# 10w_CREE_LED_driver_auto.net
KiCad netlist of a schematic drawn in EAGLE
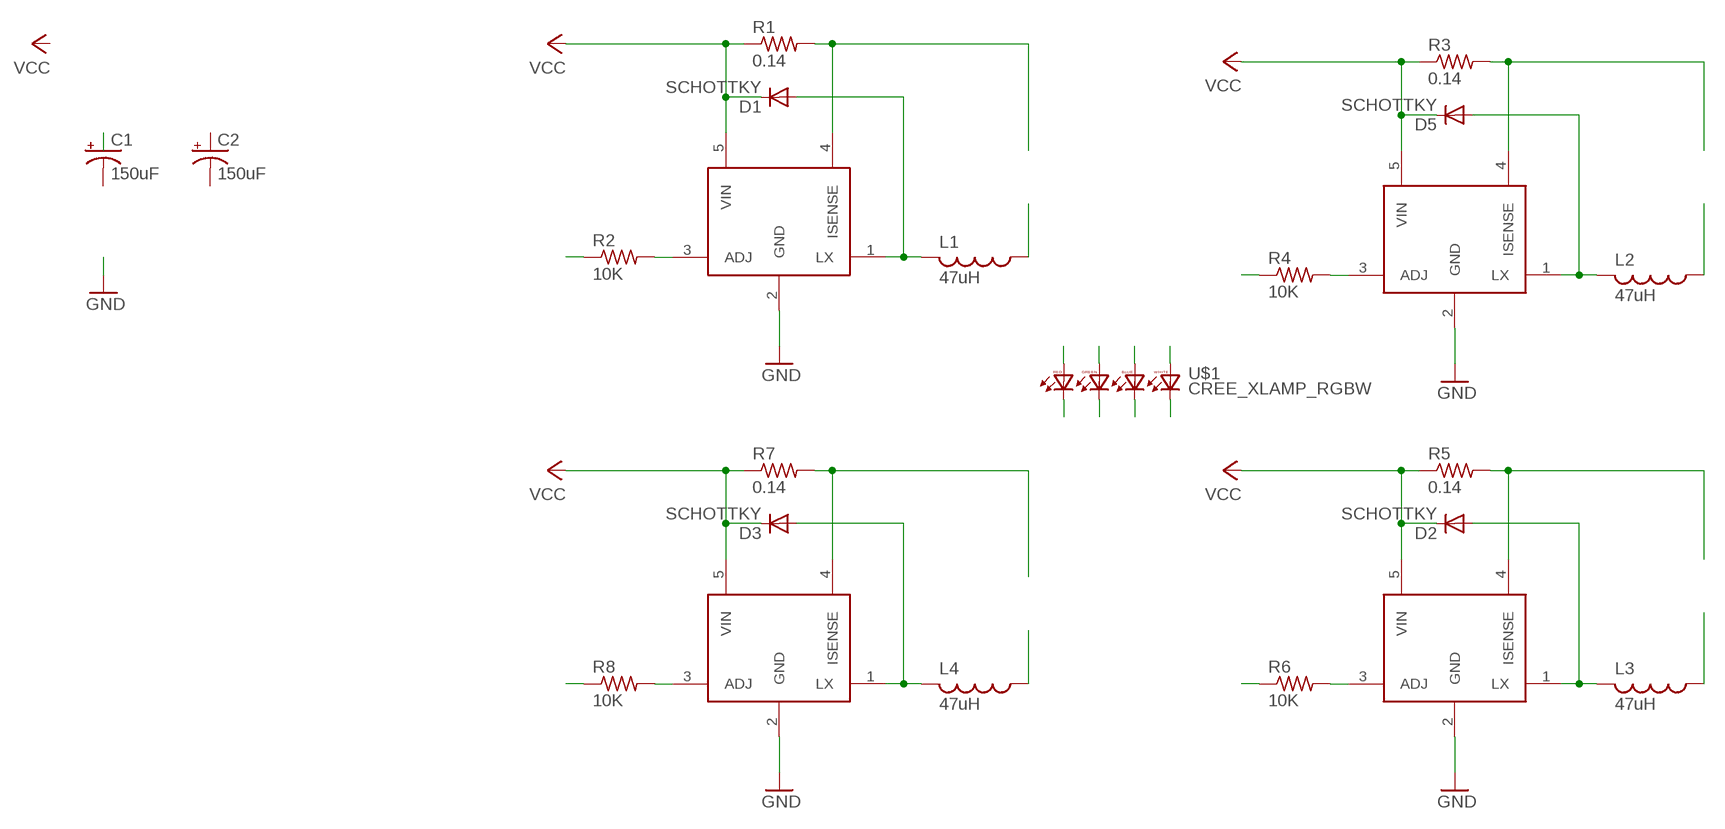
[diagram p0: schematic, sheet 1]

(export (version "E")
  (design (tool "Eeschema 10.0.6"))
  (components
    (comp (ref "C1")
      (value "150uF")
      (footprint "eagle-import:175TMP-0810")
      (libsource (lib "eagle-import") (part "CPOL-US175TMP-0810"))
    )
    (comp (ref "C2")
      (value "150uF")
      (footprint "eagle-import:175TMP-0810")
      (libsource (lib "eagle-import") (part "CPOL-US175TMP-0810"))
    )
    (comp (ref "D1")
      (value "SCHOTTKY")
      (footprint "eagle-import:DO214AC")
      (libsource (lib "eagle-import") (part "DIODE-DO214AC"))
    )
    (comp (ref "D2")
      (value "SCHOTTKY")
      (footprint "eagle-import:DO214AC")
      (libsource (lib "eagle-import") (part "DIODE-DO214AC"))
    )
    (comp (ref "D3")
      (value "SCHOTTKY")
      (footprint "eagle-import:DO214AC")
      (libsource (lib "eagle-import") (part "DIODE-DO214AC"))
    )
    (comp (ref "D5")
      (value "SCHOTTKY")
      (footprint "eagle-import:DO214AC")
      (libsource (lib "eagle-import") (part "DIODE-DO214AC"))
    )
    (comp (ref "L1")
      (value "47uH")
      (footprint "eagle-import:TDK6045")
      (libsource (lib "eagle-import") (part "L-US"))
    )
    (comp (ref "L2")
      (value "47uH")
      (footprint "eagle-import:TDK6045")
      (libsource (lib "eagle-import") (part "L-US"))
    )
    (comp (ref "L3")
      (value "47uH")
      (footprint "eagle-import:TDK6045")
      (libsource (lib "eagle-import") (part "L-US"))
    )
    (comp (ref "L4")
      (value "47uH")
      (footprint "eagle-import:TDK6045")
      (libsource (lib "eagle-import") (part "L-US"))
    )
    (comp (ref "R1")
      (value "0.14")
      (footprint "eagle-import:R0805")
      (libsource (lib "eagle-import") (part "R-US_R0805"))
    )
    (comp (ref "R2")
      (value "10K")
      (footprint "eagle-import:R0603")
      (libsource (lib "eagle-import") (part "R-US_R0603"))
    )
    (comp (ref "R3")
      (value "0.14")
      (footprint "eagle-import:R0805")
      (libsource (lib "eagle-import") (part "R-US_R0805"))
    )
    (comp (ref "R4")
      (value "10K")
      (footprint "eagle-import:R0603")
      (libsource (lib "eagle-import") (part "R-US_R0603"))
    )
    (comp (ref "R5")
      (value "0.14")
      (footprint "eagle-import:R0805")
      (libsource (lib "eagle-import") (part "R-US_R0805"))
    )
    (comp (ref "R6")
      (value "10K")
      (footprint "eagle-import:R0603")
      (libsource (lib "eagle-import") (part "R-US_R0603"))
    )
    (comp (ref "R7")
      (value "0.14")
      (footprint "eagle-import:R0805")
      (libsource (lib "eagle-import") (part "R-US_R0805"))
    )
    (comp (ref "R8")
      (value "10K")
      (footprint "eagle-import:R0603")
      (libsource (lib "eagle-import") (part "R-US_R0603"))
    )
    (comp (ref "U$1")
      (value "CREE_XLAMP_RGBW")
      (footprint "eagle-import:CREE_XLAMP_XML")
      (libsource (lib "eagle-import") (part "CREE_XLAMP_RGBW"))
    )
    (comp (ref "U$2")
      (value "ZLED7000-LEDDRIVER")
      (footprint "eagle-import:SOT89-5")
      (libsource (lib "eagle-import") (part "ZLED7000-LEDDRIVER"))
    )
    (comp (ref "U$3")
      (value "ZLED7000-LEDDRIVER")
      (footprint "eagle-import:SOT89-5")
      (libsource (lib "eagle-import") (part "ZLED7000-LEDDRIVER"))
    )
    (comp (ref "U$4")
      (value "ZLED7000-LEDDRIVER")
      (footprint "eagle-import:SOT89-5")
      (libsource (lib "eagle-import") (part "ZLED7000-LEDDRIVER"))
    )
    (comp (ref "U$6")
      (value "ZLED7000-LEDDRIVER")
      (footprint "eagle-import:SOT89-5")
      (libsource (lib "eagle-import") (part "ZLED7000-LEDDRIVER"))
    )
  )
  (nets
    (net (code "1") (name "/B+") (class "Default")
      (node (ref "R7") (pin "2") (pinfunction "2_2") (pintype "passive"))
      (node (ref "U$1") (pin "3") (pinfunction "BA_3") (pintype "passive"))
      (node (ref "U$4") (pin "4") (pinfunction "ISENSE_4") (pintype "bidirectional"))
    )
    (net (code "2") (name "/B-") (class "Default")
      (node (ref "L4") (pin "1") (pinfunction "1_1") (pintype "passive"))
      (node (ref "U$1") (pin "6") (pinfunction "BC_6") (pintype "passive"))
    )
    (net (code "3") (name "/G+") (class "Default")
      (node (ref "R1") (pin "2") (pinfunction "2_2") (pintype "passive"))
      (node (ref "U$1") (pin "2") (pinfunction "GA_2") (pintype "passive"))
      (node (ref "U$2") (pin "4") (pinfunction "ISENSE_4") (pintype "bidirectional"))
    )
    (net (code "4") (name "/G-") (class "Default")
      (node (ref "L1") (pin "1") (pinfunction "1_1") (pintype "passive"))
      (node (ref "U$1") (pin "7") (pinfunction "GC_7") (pintype "passive"))
    )
    (net (code "5") (name "/R+") (class "Default")
      (node (ref "R5") (pin "2") (pinfunction "2_2") (pintype "passive"))
      (node (ref "U$1") (pin "1") (pinfunction "RA_1") (pintype "passive"))
      (node (ref "U$3") (pin "4") (pinfunction "ISENSE_4") (pintype "bidirectional"))
    )
    (net (code "6") (name "/R-") (class "Default")
      (node (ref "L3") (pin "1") (pinfunction "1_1") (pintype "passive"))
      (node (ref "U$1") (pin "8") (pinfunction "RC_8") (pintype "passive"))
    )
    (net (code "7") (name "/W+") (class "Default")
      (node (ref "R3") (pin "2") (pinfunction "2_2") (pintype "passive"))
      (node (ref "U$1") (pin "4") (pinfunction "WA_4") (pintype "passive"))
      (node (ref "U$6") (pin "4") (pinfunction "ISENSE_4") (pintype "bidirectional"))
    )
    (net (code "8") (name "/W-") (class "Default")
      (node (ref "L2") (pin "1") (pinfunction "1_1") (pintype "passive"))
      (node (ref "U$1") (pin "5") (pinfunction "WC_5") (pintype "passive"))
    )
    (net (code "9") (name "GND") (class "Default")
      (node (ref "U$2") (pin "2") (pinfunction "GND_2") (pintype "bidirectional"))
      (node (ref "U$3") (pin "2") (pinfunction "GND_2") (pintype "bidirectional"))
      (node (ref "U$4") (pin "2") (pinfunction "GND_2") (pintype "bidirectional"))
      (node (ref "U$6") (pin "2") (pinfunction "GND_2") (pintype "bidirectional"))
    )
    (net (code "10") (name "Net-(U$2-ADJ)") (class "Default")
      (node (ref "R2") (pin "2") (pinfunction "2_2") (pintype "passive"))
      (node (ref "U$2") (pin "3") (pinfunction "ADJ_3") (pintype "bidirectional"))
    )
    (net (code "11") (name "Net-(U$2-LX)") (class "Default")
      (node (ref "D1") (pin "A") (pinfunction "A_A") (pintype "passive"))
      (node (ref "L1") (pin "2") (pinfunction "2_2") (pintype "passive"))
      (node (ref "U$2") (pin "1") (pinfunction "LX_1") (pintype "bidirectional"))
    )
    (net (code "12") (name "Net-(U$3-ADJ)") (class "Default")
      (node (ref "R6") (pin "2") (pinfunction "2_2") (pintype "passive"))
      (node (ref "U$3") (pin "3") (pinfunction "ADJ_3") (pintype "bidirectional"))
    )
    (net (code "13") (name "Net-(U$3-LX)") (class "Default")
      (node (ref "D2") (pin "A") (pinfunction "A_A") (pintype "passive"))
      (node (ref "L3") (pin "2") (pinfunction "2_2") (pintype "passive"))
      (node (ref "U$3") (pin "1") (pinfunction "LX_1") (pintype "bidirectional"))
    )
    (net (code "14") (name "Net-(U$4-ADJ)") (class "Default")
      (node (ref "R8") (pin "2") (pinfunction "2_2") (pintype "passive"))
      (node (ref "U$4") (pin "3") (pinfunction "ADJ_3") (pintype "bidirectional"))
    )
    (net (code "15") (name "Net-(U$4-LX)") (class "Default")
      (node (ref "D3") (pin "A") (pinfunction "A_A") (pintype "passive"))
      (node (ref "L4") (pin "2") (pinfunction "2_2") (pintype "passive"))
      (node (ref "U$4") (pin "1") (pinfunction "LX_1") (pintype "bidirectional"))
    )
    (net (code "16") (name "Net-(U$6-ADJ)") (class "Default")
      (node (ref "R4") (pin "2") (pinfunction "2_2") (pintype "passive"))
      (node (ref "U$6") (pin "3") (pinfunction "ADJ_3") (pintype "bidirectional"))
    )
    (net (code "17") (name "Net-(U$6-LX)") (class "Default")
      (node (ref "D5") (pin "A") (pinfunction "A_A") (pintype "passive"))
      (node (ref "L2") (pin "2") (pinfunction "2_2") (pintype "passive"))
      (node (ref "U$6") (pin "1") (pinfunction "LX_1") (pintype "bidirectional"))
    )
    (net (code "18") (name "VCC") (class "Default")
      (node (ref "D1") (pin "C") (pinfunction "C_C") (pintype "passive"))
      (node (ref "D2") (pin "C") (pinfunction "C_C") (pintype "passive"))
      (node (ref "D3") (pin "C") (pinfunction "C_C") (pintype "passive"))
      (node (ref "D5") (pin "C") (pinfunction "C_C") (pintype "passive"))
      (node (ref "R1") (pin "1") (pinfunction "1_1") (pintype "passive"))
      (node (ref "R3") (pin "1") (pinfunction "1_1") (pintype "passive"))
      (node (ref "R5") (pin "1") (pinfunction "1_1") (pintype "passive"))
      (node (ref "R7") (pin "1") (pinfunction "1_1") (pintype "passive"))
      (node (ref "U$2") (pin "5") (pinfunction "VIN_5") (pintype "bidirectional"))
      (node (ref "U$3") (pin "5") (pinfunction "VIN_5") (pintype "bidirectional"))
      (node (ref "U$4") (pin "5") (pinfunction "VIN_5") (pintype "bidirectional"))
      (node (ref "U$6") (pin "5") (pinfunction "VIN_5") (pintype "bidirectional"))
    )
    (net (code "19") (name "unconnected-(C1-Pad+)") (class "Default")
      (node (ref "C1") (pin "+") (pinfunction "+_+") (pintype "passive"))
    )
    (net (code "20") (name "unconnected-(C1-Pad-)") (class "Default")
      (node (ref "C1") (pin "-") (pinfunction "-_-") (pintype "passive"))
    )
    (net (code "21") (name "unconnected-(C2-Pad+)") (class "Default")
      (node (ref "C2") (pin "+") (pinfunction "+_+") (pintype "passive"))
    )
    (net (code "22") (name "unconnected-(C2-Pad-)") (class "Default")
      (node (ref "C2") (pin "-") (pinfunction "-_-") (pintype "passive"))
    )
    (net (code "23") (name "unconnected-(R2-Pad1)") (class "Default")
      (node (ref "R2") (pin "1") (pinfunction "1_1") (pintype "passive"))
    )
    (net (code "24") (name "unconnected-(R4-Pad1)") (class "Default")
      (node (ref "R4") (pin "1") (pinfunction "1_1") (pintype "passive"))
    )
    (net (code "25") (name "unconnected-(R6-Pad1)") (class "Default")
      (node (ref "R6") (pin "1") (pinfunction "1_1") (pintype "passive"))
    )
    (net (code "26") (name "unconnected-(R8-Pad1)") (class "Default")
      (node (ref "R8") (pin "1") (pinfunction "1_1") (pintype "passive"))
    )
  )
)
